# Power.net
KiCad netlist of a schematic drawn in Altium Designer
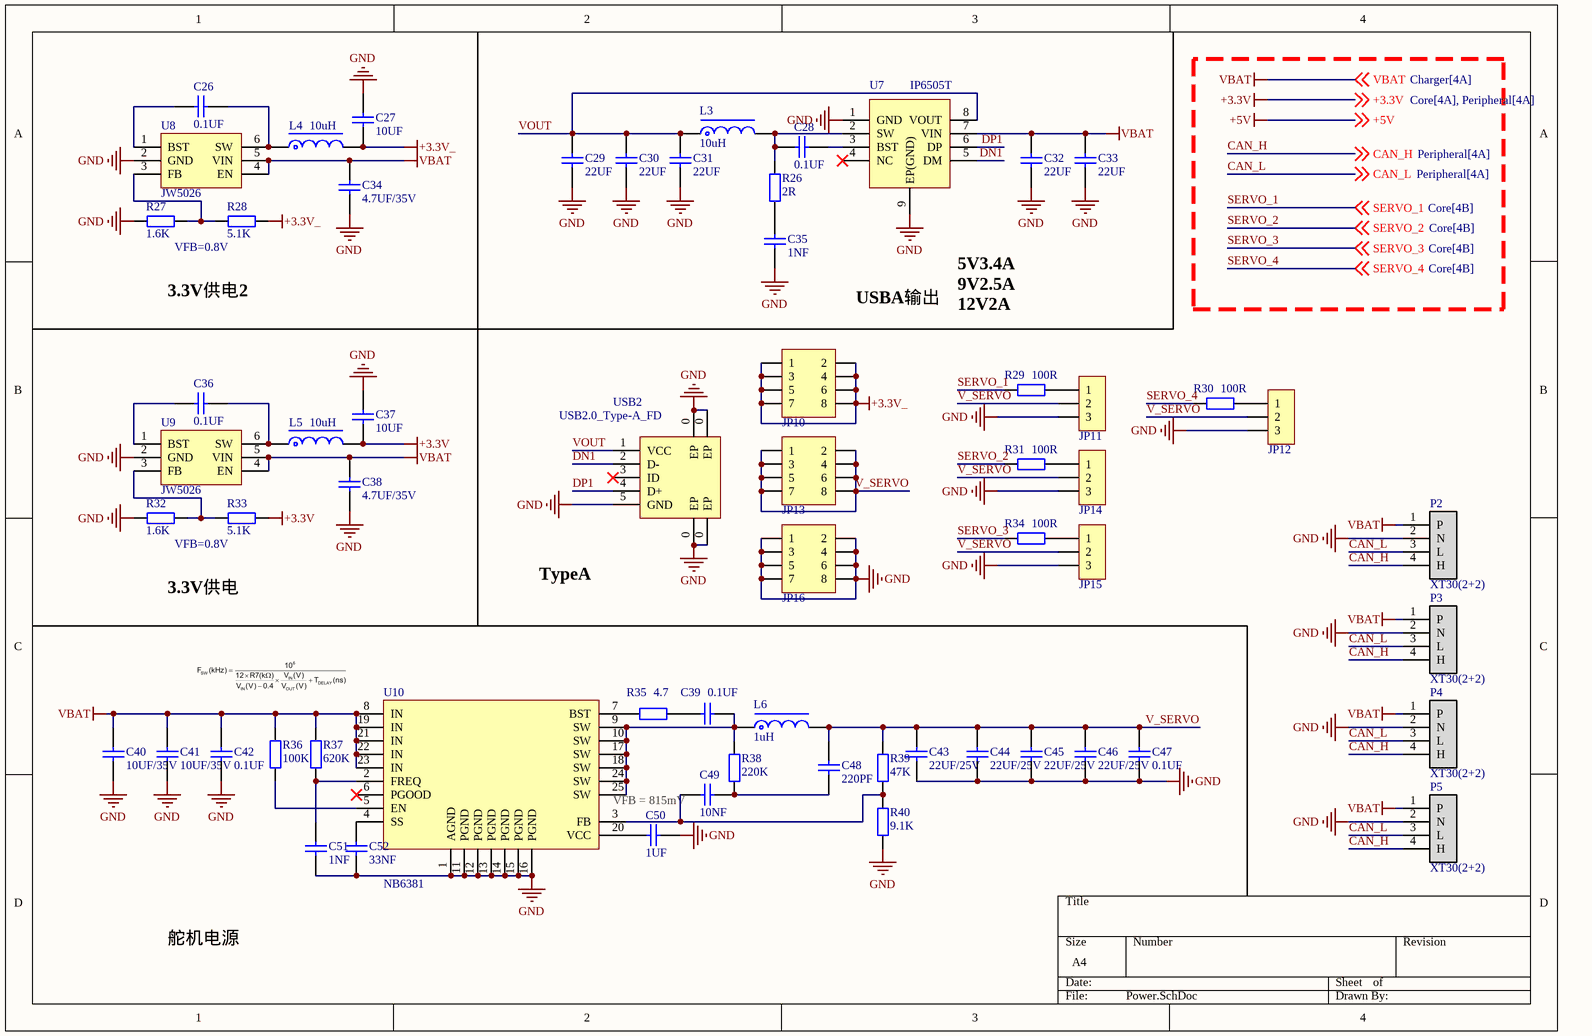
[diagram p0: Power.SchDoc]

(export (version "E")
  (design (tool "Eeschema 10.0.6"))
  (components
    (comp (ref "C26")
      (value "0.1UF")
      (footprint "C0402_NS")
      (description "贴片电容/MLCC电容")
      (libsource (lib "阻容") (part "C"))
    )
    (comp (ref "C27")
      (value "10UF")
      (footprint "C0805_NS")
      (description "贴片电容/MLCC电容")
      (libsource (lib "阻容") (part "C"))
    )
    (comp (ref "C28")
      (value "0.1UF")
      (footprint "C0402_NS")
      (description "贴片电容/MLCC电容")
      (libsource (lib "阻容") (part "C"))
    )
    (comp (ref "C29")
      (value "22UF")
      (footprint "C0805_NS")
      (description "贴片电容/MLCC电容")
      (libsource (lib "阻容") (part "C"))
    )
    (comp (ref "C30")
      (value "22UF")
      (footprint "C0805_NS")
      (description "贴片电容/MLCC电容")
      (libsource (lib "阻容") (part "C"))
    )
    (comp (ref "C31")
      (value "22UF")
      (footprint "C0805_NS")
      (description "贴片电容/MLCC电容")
      (libsource (lib "阻容") (part "C"))
    )
    (comp (ref "C32")
      (value "22UF")
      (footprint "C0805_NS")
      (description "贴片电容/MLCC电容")
      (libsource (lib "阻容") (part "C"))
    )
    (comp (ref "C33")
      (value "22UF")
      (footprint "C0805_NS")
      (description "贴片电容/MLCC电容")
      (libsource (lib "阻容") (part "C"))
    )
    (comp (ref "C34")
      (value "4.7UF/35V")
      (footprint "C0603_NS")
      (description "贴片电容/MLCC电容")
      (libsource (lib "阻容") (part "C"))
    )
    (comp (ref "C35")
      (value "1NF")
      (footprint "C0402_NS")
      (description "贴片电容/MLCC电容")
      (libsource (lib "阻容") (part "C"))
    )
    (comp (ref "C36")
      (value "0.1UF")
      (footprint "C0402_NS")
      (description "贴片电容/MLCC电容")
      (libsource (lib "阻容") (part "C"))
    )
    (comp (ref "C37")
      (value "10UF")
      (footprint "C0805_NS")
      (description "贴片电容/MLCC电容")
      (libsource (lib "阻容") (part "C"))
    )
    (comp (ref "C38")
      (value "4.7UF/35V")
      (footprint "C0603_NS")
      (description "贴片电容/MLCC电容")
      (libsource (lib "阻容") (part "C"))
    )
    (comp (ref "C39")
      (value "0.1UF")
      (footprint "C0402_NS")
      (description "贴片电容/MLCC电容")
      (libsource (lib "阻容") (part "C"))
    )
    (comp (ref "C40")
      (value "10UF/35V")
      (footprint "C0805_NS")
      (description "贴片电容/MLCC电容")
      (libsource (lib "阻容") (part "C"))
    )
    (comp (ref "C41")
      (value "10UF/35V")
      (footprint "C0805_NS")
      (description "贴片电容/MLCC电容")
      (libsource (lib "阻容") (part "C"))
    )
    (comp (ref "C42")
      (value "0.1UF")
      (footprint "C0603_NS")
      (description "贴片电容/MLCC电容")
      (libsource (lib "阻容") (part "C"))
    )
    (comp (ref "C43")
      (value "22UF/25V")
      (footprint "C0805_NS")
      (description "贴片电容/MLCC电容")
      (libsource (lib "阻容") (part "C"))
    )
    (comp (ref "C44")
      (value "22UF/25V")
      (footprint "C0805_NS")
      (description "贴片电容/MLCC电容")
      (libsource (lib "阻容") (part "C"))
    )
    (comp (ref "C45")
      (value "22UF/25V")
      (footprint "C0805_NS")
      (description "贴片电容/MLCC电容")
      (libsource (lib "阻容") (part "C"))
    )
    (comp (ref "C46")
      (value "22UF/25V")
      (footprint "C0805_NS")
      (description "贴片电容/MLCC电容")
      (libsource (lib "阻容") (part "C"))
    )
    (comp (ref "C47")
      (value "0.1UF")
      (footprint "C0402_NS")
      (description "贴片电容/MLCC电容")
      (libsource (lib "阻容") (part "C"))
    )
    (comp (ref "C48")
      (value "220PF")
      (footprint "C0402_NS")
      (description "贴片电容/MLCC电容")
      (libsource (lib "阻容") (part "C"))
    )
    (comp (ref "C49")
      (value "10NF")
      (footprint "C0402_NS")
      (description "贴片电容/MLCC电容")
      (libsource (lib "阻容") (part "C"))
    )
    (comp (ref "C50")
      (value "1UF")
      (footprint "C0402_NS")
      (description "贴片电容/MLCC电容")
      (libsource (lib "阻容") (part "C"))
    )
    (comp (ref "C51")
      (value "1NF")
      (footprint "C0402_NS")
      (description "贴片电容/MLCC电容")
      (libsource (lib "阻容") (part "C"))
    )
    (comp (ref "C52")
      (value "33NF")
      (footprint "C0402_NS")
      (description "贴片电容/MLCC电容")
      (libsource (lib "阻容") (part "C"))
    )
    (comp (ref "JP10")
      (value "Header 4X2")
      (footprint "HDR2.54-LI-2x4P")
      (description "4*2P接插件")
      (libsource (lib "2.54mm连接器") (part "Header 4X2"))
    )
    (comp (ref "JP11")
      (value "HDR-1X3")
      (footprint "HDR2.54-LI-3P")
      (description "3P接插件")
      (libsource (lib "2.54mm连接器") (part "Header 3"))
    )
    (comp (ref "JP12")
      (value "HDR-1X3")
      (footprint "HDR2.54-LI-3P")
      (description "3P接插件")
      (libsource (lib "2.54mm连接器") (part "Header 3"))
    )
    (comp (ref "JP13")
      (value "Header 4X2")
      (footprint "HDR2.54-LI-2x4P")
      (description "4*2P接插件")
      (libsource (lib "2.54mm连接器") (part "Header 4X2"))
    )
    (comp (ref "JP14")
      (value "HDR-1X3")
      (footprint "HDR2.54-LI-3P")
      (description "3P接插件")
      (libsource (lib "2.54mm连接器") (part "Header 3"))
    )
    (comp (ref "JP15")
      (value "HDR-1X3")
      (footprint "HDR2.54-LI-3P")
      (description "3P接插件")
      (libsource (lib "2.54mm连接器") (part "Header 3"))
    )
    (comp (ref "JP16")
      (value "Header 4X2")
      (footprint "HDR2.54-LI-2x4P")
      (description "4*2P接插件")
      (libsource (lib "2.54mm连接器") (part "Header 4X2"))
    )
    (comp (ref "L3")
      (value "10uH")
      (footprint "L-SMD-0630")
      (description "一体成型电感")
      (libsource (lib "电感") (part "L-Molding Choke"))
    )
    (comp (ref "L4")
      (value "10uH")
      (footprint "L-SMD-0420")
      (description "一体成型电感")
      (libsource (lib "电感") (part "L-Molding Choke"))
    )
    (comp (ref "L5")
      (value "10uH")
      (footprint "L-SMD-0420")
      (description "一体成型电感")
      (libsource (lib "电感") (part "L-Molding Choke"))
    )
    (comp (ref "L6")
      (value "1uH")
      (footprint "L-SMD-0630")
      (description "一体成型电感")
      (libsource (lib "电感") (part "L-Molding Choke"))
    )
    (comp (ref "P2")
      (value "XT30(2+2)")
      (footprint "XT30(2+2)PW-M")
      (description "XT30(2+2)连接器")
      (libsource (lib "接口") (part "XT30(2+2)"))
    )
    (comp (ref "P3")
      (value "XT30(2+2)")
      (footprint "XT30(2+2)PW-M")
      (description "XT30(2+2)连接器")
      (libsource (lib "接口") (part "XT30(2+2)"))
    )
    (comp (ref "P4")
      (value "XT30(2+2)")
      (footprint "XT30(2+2)PW-M")
      (description "XT30(2+2)连接器")
      (libsource (lib "接口") (part "XT30(2+2)"))
    )
    (comp (ref "P5")
      (value "XT30(2+2)")
      (footprint "XT30(2+2)PW-M")
      (description "XT30(2+2)连接器")
      (libsource (lib "接口") (part "XT30(2+2)"))
    )
    (comp (ref "R26")
      (value "2R")
      (footprint "R0402_NS")
      (description "贴片电阻")
      (libsource (lib "阻容") (part "R"))
    )
    (comp (ref "R27")
      (value "1.6K")
      (footprint "R0402_NS")
      (description "贴片电阻")
      (libsource (lib "阻容") (part "R"))
    )
    (comp (ref "R28")
      (value "5.1K")
      (footprint "R0402_NS")
      (description "贴片电阻")
      (libsource (lib "阻容") (part "R"))
    )
    (comp (ref "R29")
      (value "100R")
      (footprint "R0402_NS")
      (description "贴片电阻")
      (libsource (lib "阻容") (part "R"))
    )
    (comp (ref "R30")
      (value "100R")
      (footprint "R0402_NS")
      (description "贴片电阻")
      (libsource (lib "阻容") (part "R"))
    )
    (comp (ref "R31")
      (value "100R")
      (footprint "R0402_NS")
      (description "贴片电阻")
      (libsource (lib "阻容") (part "R"))
    )
    (comp (ref "R32")
      (value "1.6K")
      (footprint "R0402_NS")
      (description "贴片电阻")
      (libsource (lib "阻容") (part "R"))
    )
    (comp (ref "R33")
      (value "5.1K")
      (footprint "R0402_NS")
      (description "贴片电阻")
      (libsource (lib "阻容") (part "R"))
    )
    (comp (ref "R34")
      (value "100R")
      (footprint "R0402_NS")
      (description "贴片电阻")
      (libsource (lib "阻容") (part "R"))
    )
    (comp (ref "R35")
      (value "4.7")
      (footprint "R0402_NS")
      (description "贴片电阻")
      (libsource (lib "阻容") (part "R"))
    )
    (comp (ref "R36")
      (value "100K")
      (footprint "R0402_NS")
      (description "贴片电阻")
      (libsource (lib "阻容") (part "R"))
    )
    (comp (ref "R37")
      (value "620K")
      (footprint "R0402_NS")
      (description "贴片电阻")
      (libsource (lib "阻容") (part "R"))
    )
    (comp (ref "R38")
      (value "220K")
      (footprint "R0402_NS")
      (description "贴片电阻")
      (libsource (lib "阻容") (part "R"))
    )
    (comp (ref "R39")
      (value "47K")
      (footprint "R0402_NS")
      (description "贴片电阻")
      (libsource (lib "阻容") (part "R"))
    )
    (comp (ref "R40")
      (value "9.1K")
      (footprint "R0402_NS")
      (description "贴片电阻")
      (libsource (lib "阻容") (part "R"))
    )
    (comp (ref "U7")
      (value "IP6505T")
      (footprint "ESOP8_L5.0_W6.0_P1.27")
      (description "最大输出 24W，集成各种快充输出协议(DCP/QC2.0/QC3.0/FCP/AFC/SFCP)的 SOC IC")
      (libsource (lib "电源IC") (part "IP6505T"))
    )
    (comp (ref "U8")
      (value "JW5026")
      (footprint "SOT23-6_L3.0_W1.7_P0.95")
      (description "40V/1A/1.1MHz同步降压转换器")
      (libsource (lib "电源IC") (part "JW5026"))
    )
    (comp (ref "U9")
      (value "JW5026")
      (footprint "SOT23-6_L3.0_W1.7_P0.95")
      (description "40V/1A/1.1MHz同步降压转换器")
      (libsource (lib "电源IC") (part "JW5026"))
    )
    (comp (ref "U10")
      (value "NB6381")
      (footprint "QFN20_L3.0_W4.0-P0.50")
      (description "Wide Vin 4.5-28V, 8A, COT Synchronous Step-Down Converter with Internal Bias Supply")
      (libsource (lib "Schlib1") (part "NB6381"))
    )
    (comp (ref "USB2")
      (value "USB2.0_Type-A_FD")
      (footprint "USB2.0_Type-A_SMD_FD")
      (description "USB2.0_Type-A母座,带ID")
      (libsource (lib "接口") (part "USB2.0_Type-A_FD"))
    )
  )
  (nets
    (net (code "1") (name "+3.3V") (class "Default")
      (node (ref "C37") (pin "2") (pinfunction "2_2") (pintype "passive"))
      (node (ref "L5") (pin "2") (pinfunction "2_2") (pintype "passive"))
      (node (ref "R33") (pin "1") (pinfunction "1_1") (pintype "passive"))
    )
    (net (code "2") (name "+3.3V_") (class "Default")
      (node (ref "C27") (pin "2") (pinfunction "2_2") (pintype "passive"))
      (node (ref "JP10") (pin "1") (pinfunction "1_1") (pintype "passive"))
      (node (ref "JP10") (pin "2") (pinfunction "2_2") (pintype "passive"))
      (node (ref "JP10") (pin "3") (pinfunction "3_3") (pintype "passive"))
      (node (ref "JP10") (pin "4") (pinfunction "4_4") (pintype "passive"))
      (node (ref "JP10") (pin "5") (pinfunction "5_5") (pintype "passive"))
      (node (ref "JP10") (pin "6") (pinfunction "6_6") (pintype "passive"))
      (node (ref "JP10") (pin "7") (pinfunction "7_7") (pintype "passive"))
      (node (ref "JP10") (pin "8") (pinfunction "8_8") (pintype "passive"))
      (node (ref "L4") (pin "2") (pinfunction "2_2") (pintype "passive"))
      (node (ref "R28") (pin "1") (pinfunction "1_1") (pintype "passive"))
    )
    (net (code "4") (name "/DN1") (class "Default")
      (node (ref "U7") (pin "5") (pinfunction "DM_5") (pintype "passive"))
      (node (ref "USB2") (pin "2") (pinfunction "D-_2") (pintype "passive"))
    )
    (net (code "5") (name "/DP1") (class "Default")
      (node (ref "U7") (pin "6") (pinfunction "DP_6") (pintype "passive"))
      (node (ref "USB2") (pin "4") (pinfunction "D+_4") (pintype "passive"))
    )
    (net (code "6") (name "/VOUT") (class "Default")
      (node (ref "C29") (pin "2") (pinfunction "2_2") (pintype "passive"))
      (node (ref "C30") (pin "2") (pinfunction "2_2") (pintype "passive"))
      (node (ref "C31") (pin "2") (pinfunction "2_2") (pintype "passive"))
      (node (ref "L3") (pin "1") (pinfunction "1_1") (pintype "passive"))
      (node (ref "U7") (pin "8") (pinfunction "VOUT_8") (pintype "passive"))
      (node (ref "USB2") (pin "1") (pinfunction "VCC_1") (pintype "passive"))
    )
    (net (code "7") (name "/V_SERVO") (class "Default")
      (node (ref "C43") (pin "2") (pinfunction "2_2") (pintype "passive"))
      (node (ref "C44") (pin "2") (pinfunction "2_2") (pintype "passive"))
      (node (ref "C45") (pin "2") (pinfunction "2_2") (pintype "passive"))
      (node (ref "C46") (pin "2") (pinfunction "2_2") (pintype "passive"))
      (node (ref "C47") (pin "1") (pinfunction "1_1") (pintype "passive"))
      (node (ref "C48") (pin "2") (pinfunction "2_2") (pintype "passive"))
      (node (ref "JP11") (pin "2") (pinfunction "2_2") (pintype "passive"))
      (node (ref "JP12") (pin "2") (pinfunction "2_2") (pintype "passive"))
      (node (ref "JP13") (pin "1") (pinfunction "1_1") (pintype "passive"))
      (node (ref "JP13") (pin "2") (pinfunction "2_2") (pintype "passive"))
      (node (ref "JP13") (pin "3") (pinfunction "3_3") (pintype "passive"))
      (node (ref "JP13") (pin "4") (pinfunction "4_4") (pintype "passive"))
      (node (ref "JP13") (pin "5") (pinfunction "5_5") (pintype "passive"))
      (node (ref "JP13") (pin "6") (pinfunction "6_6") (pintype "passive"))
      (node (ref "JP13") (pin "7") (pinfunction "7_7") (pintype "passive"))
      (node (ref "JP13") (pin "8") (pinfunction "8_8") (pintype "passive"))
      (node (ref "JP14") (pin "2") (pinfunction "2_2") (pintype "passive"))
      (node (ref "JP15") (pin "2") (pinfunction "2_2") (pintype "passive"))
      (node (ref "L6") (pin "2") (pinfunction "2_2") (pintype "passive"))
      (node (ref "R39") (pin "2") (pinfunction "2_2") (pintype "passive"))
    )
    (net (code "8") (name "CAN_H") (class "Default")
      (node (ref "P2") (pin "4") (pinfunction "H_4") (pintype "passive"))
      (node (ref "P3") (pin "4") (pinfunction "H_4") (pintype "passive"))
      (node (ref "P4") (pin "4") (pinfunction "H_4") (pintype "passive"))
      (node (ref "P5") (pin "4") (pinfunction "H_4") (pintype "passive"))
    )
    (net (code "9") (name "CAN_L") (class "Default")
      (node (ref "P2") (pin "3") (pinfunction "L_3") (pintype "passive"))
      (node (ref "P3") (pin "3") (pinfunction "L_3") (pintype "passive"))
      (node (ref "P4") (pin "3") (pinfunction "L_3") (pintype "passive"))
      (node (ref "P5") (pin "3") (pinfunction "L_3") (pintype "passive"))
    )
    (net (code "10") (name "GND") (class "Default")
      (node (ref "C27") (pin "1") (pinfunction "1_1") (pintype "passive"))
      (node (ref "C29") (pin "1") (pinfunction "1_1") (pintype "passive"))
      (node (ref "C30") (pin "1") (pinfunction "1_1") (pintype "passive"))
      (node (ref "C31") (pin "1") (pinfunction "1_1") (pintype "passive"))
      (node (ref "C32") (pin "1") (pinfunction "1_1") (pintype "passive"))
      (node (ref "C33") (pin "1") (pinfunction "1_1") (pintype "passive"))
      (node (ref "C34") (pin "1") (pinfunction "1_1") (pintype "passive"))
      (node (ref "C35") (pin "1") (pinfunction "1_1") (pintype "passive"))
      (node (ref "C37") (pin "1") (pinfunction "1_1") (pintype "passive"))
      (node (ref "C38") (pin "1") (pinfunction "1_1") (pintype "passive"))
      (node (ref "C40") (pin "1") (pinfunction "1_1") (pintype "passive"))
      (node (ref "C41") (pin "1") (pinfunction "1_1") (pintype "passive"))
      (node (ref "C42") (pin "2") (pinfunction "2_2") (pintype "passive"))
      (node (ref "C43") (pin "1") (pinfunction "1_1") (pintype "passive"))
      (node (ref "C44") (pin "1") (pinfunction "1_1") (pintype "passive"))
      (node (ref "C45") (pin "1") (pinfunction "1_1") (pintype "passive"))
      (node (ref "C46") (pin "1") (pinfunction "1_1") (pintype "passive"))
      (node (ref "C47") (pin "2") (pinfunction "2_2") (pintype "passive"))
      (node (ref "C50") (pin "1") (pinfunction "1_1") (pintype "passive"))
      (node (ref "C51") (pin "2") (pinfunction "2_2") (pintype "passive"))
      (node (ref "C52") (pin "2") (pinfunction "2_2") (pintype "passive"))
      (node (ref "JP11") (pin "3") (pinfunction "3_3") (pintype "passive"))
      (node (ref "JP12") (pin "3") (pinfunction "3_3") (pintype "passive"))
      (node (ref "JP14") (pin "3") (pinfunction "3_3") (pintype "passive"))
      (node (ref "JP15") (pin "3") (pinfunction "3_3") (pintype "passive"))
      (node (ref "JP16") (pin "1") (pinfunction "1_1") (pintype "passive"))
      (node (ref "JP16") (pin "2") (pinfunction "2_2") (pintype "passive"))
      (node (ref "JP16") (pin "3") (pinfunction "3_3") (pintype "passive"))
      (node (ref "JP16") (pin "4") (pinfunction "4_4") (pintype "passive"))
      (node (ref "JP16") (pin "5") (pinfunction "5_5") (pintype "passive"))
      (node (ref "JP16") (pin "6") (pinfunction "6_6") (pintype "passive"))
      (node (ref "JP16") (pin "7") (pinfunction "7_7") (pintype "passive"))
      (node (ref "JP16") (pin "8") (pinfunction "8_8") (pintype "passive"))
      (node (ref "P2") (pin "2") (pinfunction "N_2") (pintype "passive"))
      (node (ref "P3") (pin "2") (pinfunction "N_2") (pintype "passive"))
      (node (ref "P4") (pin "2") (pinfunction "N_2") (pintype "passive"))
      (node (ref "P5") (pin "2") (pinfunction "N_2") (pintype "passive"))
      (node (ref "R27") (pin "2") (pinfunction "2_2") (pintype "passive"))
      (node (ref "R32") (pin "2") (pinfunction "2_2") (pintype "passive"))
      (node (ref "R40") (pin "1") (pinfunction "1_1") (pintype "passive"))
      (node (ref "U10") (pin "1") (pinfunction "AGND_1") (pintype "passive"))
      (node (ref "U10") (pin "11") (pinfunction "PGND_11") (pintype "passive"))
      (node (ref "U10") (pin "12") (pinfunction "PGND_12") (pintype "passive"))
      (node (ref "U10") (pin "13") (pinfunction "PGND_13") (pintype "passive"))
      (node (ref "U10") (pin "14") (pinfunction "PGND_14") (pintype "passive"))
      (node (ref "U10") (pin "15") (pinfunction "PGND_15") (pintype "passive"))
      (node (ref "U10") (pin "16") (pinfunction "PGND_16") (pintype "passive"))
      (node (ref "U7") (pin "1") (pinfunction "GND_1") (pintype "passive"))
      (node (ref "U7") (pin "9") (pinfunction "EP(GND)_9") (pintype "passive"))
      (node (ref "U8") (pin "2") (pinfunction "GND_2") (pintype "passive"))
      (node (ref "U9") (pin "2") (pinfunction "GND_2") (pintype "passive"))
      (node (ref "USB2") (pin "0") (pinfunction "EP_0") (pintype "passive"))
      (node (ref "USB2") (pin "5") (pinfunction "GND_5") (pintype "passive"))
    )
    (net (code "11") (name "Net-(C35-Pad2)") (class "Default")
      (node (ref "C35") (pin "2") (pinfunction "2_2") (pintype "passive"))
      (node (ref "R26") (pin "1") (pinfunction "1_1") (pintype "passive"))
    )
    (net (code "12") (name "Net-(C39-Pad1)") (class "Default")
      (node (ref "C39") (pin "1") (pinfunction "1_1") (pintype "passive"))
      (node (ref "L6") (pin "1") (pinfunction "1_1") (pintype "passive"))
      (node (ref "R38") (pin "2") (pinfunction "2_2") (pintype "passive"))
      (node (ref "U10") (pin "10") (pinfunction "SW_10") (pintype "passive"))
      (node (ref "U10") (pin "17") (pinfunction "SW_17") (pintype "passive"))
      (node (ref "U10") (pin "18") (pinfunction "SW_18") (pintype "passive"))
      (node (ref "U10") (pin "24") (pinfunction "SW_24") (pintype "passive"))
      (node (ref "U10") (pin "25") (pinfunction "SW_25") (pintype "passive"))
      (node (ref "U10") (pin "9") (pinfunction "SW_9") (pintype "passive"))
    )
    (net (code "13") (name "Net-(C39-Pad2)") (class "Default")
      (node (ref "C39") (pin "2") (pinfunction "2_2") (pintype "passive"))
      (node (ref "R35") (pin "2") (pinfunction "2_2") (pintype "passive"))
    )
    (net (code "14") (name "Net-(C48-Pad1)") (class "Default")
      (node (ref "C48") (pin "1") (pinfunction "1_1") (pintype "passive"))
      (node (ref "C49") (pin "1") (pinfunction "1_1") (pintype "passive"))
      (node (ref "R38") (pin "1") (pinfunction "1_1") (pintype "passive"))
    )
    (net (code "15") (name "Net-(JP11-Pad1)") (class "Default")
      (node (ref "JP11") (pin "1") (pinfunction "1_1") (pintype "passive"))
      (node (ref "R29") (pin "2") (pinfunction "2_2") (pintype "passive"))
    )
    (net (code "16") (name "Net-(JP12-Pad1)") (class "Default")
      (node (ref "JP12") (pin "1") (pinfunction "1_1") (pintype "passive"))
      (node (ref "R30") (pin "2") (pinfunction "2_2") (pintype "passive"))
    )
    (net (code "17") (name "Net-(JP14-Pad1)") (class "Default")
      (node (ref "JP14") (pin "1") (pinfunction "1_1") (pintype "passive"))
      (node (ref "R31") (pin "2") (pinfunction "2_2") (pintype "passive"))
    )
    (net (code "18") (name "Net-(JP15-Pad1)") (class "Default")
      (node (ref "JP15") (pin "1") (pinfunction "1_1") (pintype "passive"))
      (node (ref "R34") (pin "2") (pinfunction "2_2") (pintype "passive"))
    )
    (net (code "19") (name "Net-(U7-BST)") (class "Default")
      (node (ref "C28") (pin "2") (pinfunction "2_2") (pintype "passive"))
      (node (ref "U7") (pin "3") (pinfunction "BST_3") (pintype "passive"))
    )
    (net (code "20") (name "Net-(U7-SW)") (class "Default")
      (node (ref "C28") (pin "1") (pinfunction "1_1") (pintype "passive"))
      (node (ref "L3") (pin "2") (pinfunction "2_2") (pintype "passive"))
      (node (ref "R26") (pin "2") (pinfunction "2_2") (pintype "passive"))
      (node (ref "U7") (pin "2") (pinfunction "SW_2") (pintype "passive"))
    )
    (net (code "21") (name "Net-(U8-BST)") (class "Default")
      (node (ref "C26") (pin "1") (pinfunction "1_1") (pintype "passive"))
      (node (ref "U8") (pin "1") (pinfunction "BST_1") (pintype "passive"))
    )
    (net (code "22") (name "Net-(U8-FB)") (class "Default")
      (node (ref "R27") (pin "1") (pinfunction "1_1") (pintype "passive"))
      (node (ref "R28") (pin "2") (pinfunction "2_2") (pintype "passive"))
      (node (ref "U8") (pin "3") (pinfunction "FB_3") (pintype "passive"))
    )
    (net (code "23") (name "Net-(U8-SW)") (class "Default")
      (node (ref "C26") (pin "2") (pinfunction "2_2") (pintype "passive"))
      (node (ref "L4") (pin "1") (pinfunction "1_1") (pintype "passive"))
      (node (ref "U8") (pin "6") (pinfunction "SW_6") (pintype "passive"))
    )
    (net (code "24") (name "Net-(U9-BST)") (class "Default")
      (node (ref "C36") (pin "1") (pinfunction "1_1") (pintype "passive"))
      (node (ref "U9") (pin "1") (pinfunction "BST_1") (pintype "passive"))
    )
    (net (code "25") (name "Net-(U9-FB)") (class "Default")
      (node (ref "R32") (pin "1") (pinfunction "1_1") (pintype "passive"))
      (node (ref "R33") (pin "2") (pinfunction "2_2") (pintype "passive"))
      (node (ref "U9") (pin "3") (pinfunction "FB_3") (pintype "passive"))
    )
    (net (code "26") (name "Net-(U9-SW)") (class "Default")
      (node (ref "C36") (pin "2") (pinfunction "2_2") (pintype "passive"))
      (node (ref "L5") (pin "1") (pinfunction "1_1") (pintype "passive"))
      (node (ref "U9") (pin "6") (pinfunction "SW_6") (pintype "passive"))
    )
    (net (code "27") (name "Net-(U10-BST)") (class "Default")
      (node (ref "R35") (pin "1") (pinfunction "1_1") (pintype "passive"))
      (node (ref "U10") (pin "7") (pinfunction "BST_7") (pintype "passive"))
    )
    (net (code "28") (name "Net-(U10-EN)") (class "Default")
      (node (ref "R36") (pin "1") (pinfunction "1_1") (pintype "passive"))
      (node (ref "U10") (pin "5") (pinfunction "EN_5") (pintype "passive"))
    )
    (net (code "29") (name "Net-(U10-FB)") (class "Default")
      (node (ref "C49") (pin "2") (pinfunction "2_2") (pintype "passive"))
      (node (ref "R39") (pin "1") (pinfunction "1_1") (pintype "passive"))
      (node (ref "R40") (pin "2") (pinfunction "2_2") (pintype "passive"))
      (node (ref "U10") (pin "3") (pinfunction "FB_3") (pintype "passive"))
    )
    (net (code "30") (name "Net-(U10-FREQ)") (class "Default")
      (node (ref "C51") (pin "1") (pinfunction "1_1") (pintype "passive"))
      (node (ref "R37") (pin "2") (pinfunction "2_2") (pintype "passive"))
      (node (ref "U10") (pin "2") (pinfunction "FREQ_2") (pintype "passive"))
    )
    (net (code "31") (name "Net-(U10-SS)") (class "Default")
      (node (ref "C52") (pin "1") (pinfunction "1_1") (pintype "passive"))
      (node (ref "U10") (pin "4") (pinfunction "SS_4") (pintype "passive"))
    )
    (net (code "32") (name "Net-(U10-VCC)") (class "Default")
      (node (ref "C50") (pin "2") (pinfunction "2_2") (pintype "passive"))
      (node (ref "U10") (pin "20") (pinfunction "VCC_20") (pintype "passive"))
    )
    (net (code "33") (name "SERVO_1") (class "Default")
      (node (ref "R29") (pin "1") (pinfunction "1_1") (pintype "passive"))
    )
    (net (code "34") (name "SERVO_2") (class "Default")
      (node (ref "R31") (pin "1") (pinfunction "1_1") (pintype "passive"))
    )
    (net (code "35") (name "SERVO_3") (class "Default")
      (node (ref "R34") (pin "1") (pinfunction "1_1") (pintype "passive"))
    )
    (net (code "36") (name "SERVO_4") (class "Default")
      (node (ref "R30") (pin "1") (pinfunction "1_1") (pintype "passive"))
    )
    (net (code "37") (name "VBAT") (class "Default")
      (node (ref "C32") (pin "2") (pinfunction "2_2") (pintype "passive"))
      (node (ref "C33") (pin "2") (pinfunction "2_2") (pintype "passive"))
      (node (ref "C34") (pin "2") (pinfunction "2_2") (pintype "passive"))
      (node (ref "C38") (pin "2") (pinfunction "2_2") (pintype "passive"))
      (node (ref "C40") (pin "2") (pinfunction "2_2") (pintype "passive"))
      (node (ref "C41") (pin "2") (pinfunction "2_2") (pintype "passive"))
      (node (ref "C42") (pin "1") (pinfunction "1_1") (pintype "passive"))
      (node (ref "P2") (pin "1") (pinfunction "P_1") (pintype "passive"))
      (node (ref "P3") (pin "1") (pinfunction "P_1") (pintype "passive"))
      (node (ref "P4") (pin "1") (pinfunction "P_1") (pintype "passive"))
      (node (ref "P5") (pin "1") (pinfunction "P_1") (pintype "passive"))
      (node (ref "R36") (pin "2") (pinfunction "2_2") (pintype "passive"))
      (node (ref "R37") (pin "1") (pinfunction "1_1") (pintype "passive"))
      (node (ref "U10") (pin "19") (pinfunction "IN_19") (pintype "passive"))
      (node (ref "U10") (pin "21") (pinfunction "IN_21") (pintype "passive"))
      (node (ref "U10") (pin "22") (pinfunction "IN_22") (pintype "passive"))
      (node (ref "U10") (pin "23") (pinfunction "IN_23") (pintype "passive"))
      (node (ref "U10") (pin "8") (pinfunction "IN_8") (pintype "passive"))
      (node (ref "U7") (pin "7") (pinfunction "VIN_7") (pintype "passive"))
      (node (ref "U8") (pin "4") (pinfunction "EN_4") (pintype "passive"))
      (node (ref "U8") (pin "5") (pinfunction "VIN_5") (pintype "passive"))
      (node (ref "U9") (pin "4") (pinfunction "EN_4") (pintype "passive"))
      (node (ref "U9") (pin "5") (pinfunction "VIN_5") (pintype "passive"))
    )
    (net (code "38") (name "unconnected-(U7-NC-Pad4)") (class "Default")
      (node (ref "U7") (pin "4") (pinfunction "NC_4") (pintype "passive+no_connect"))
    )
    (net (code "39") (name "unconnected-(U10-PGOOD-Pad6)") (class "Default")
      (node (ref "U10") (pin "6") (pinfunction "PGOOD_6") (pintype "passive+no_connect"))
    )
    (net (code "40") (name "unconnected-(USB2-ID-Pad3)") (class "Default")
      (node (ref "USB2") (pin "3") (pinfunction "ID_3") (pintype "passive+no_connect"))
    )
  )
)
